# 3Phase_Inverter1.net
KiCad netlist of a schematic drawn in Altium Designer
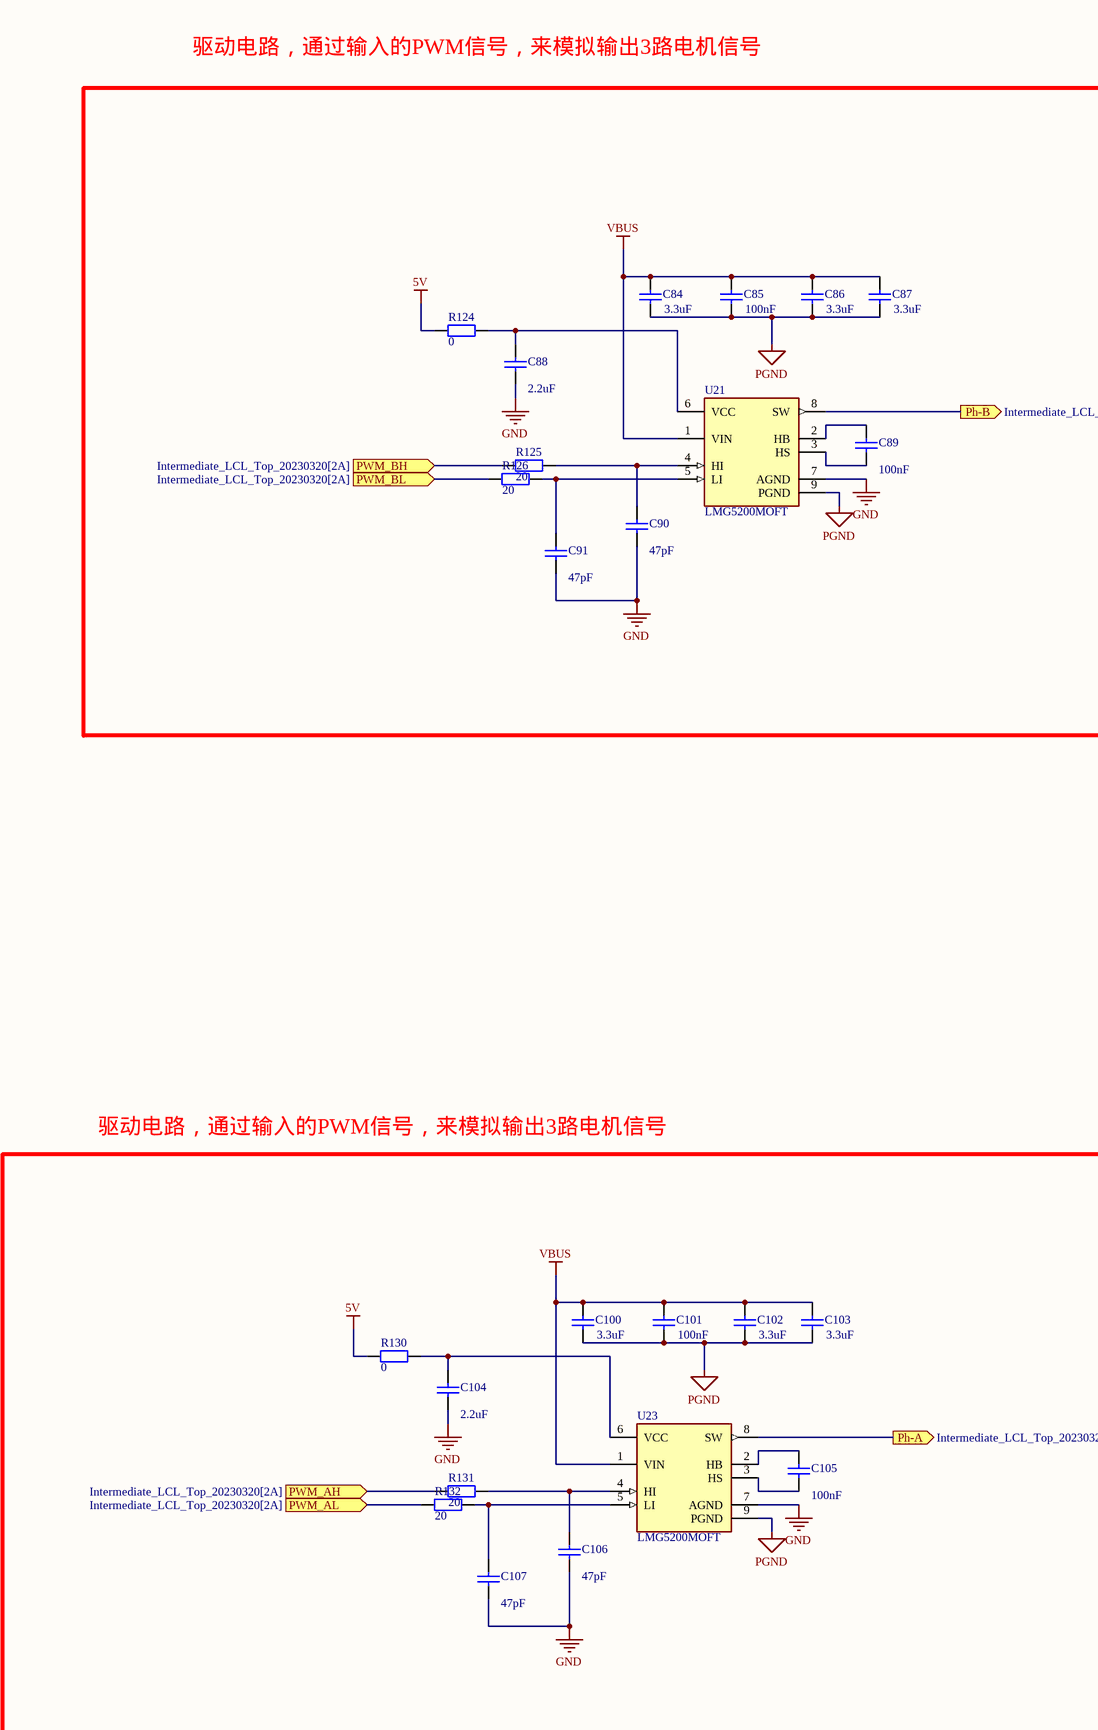
[diagram p0: 3Phase Inverter1.SchDoc, left]
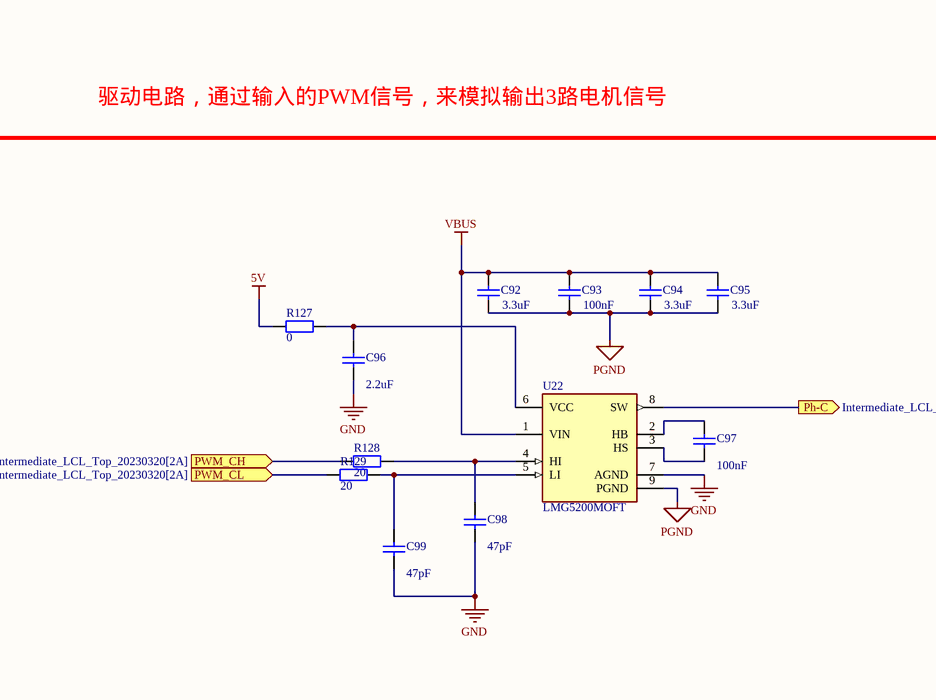
[diagram p1: 3Phase Inverter1.SchDoc, right]

(export (version "E")
  (design (tool "Eeschema 10.0.6"))
  (components
    (comp (ref "C84")
      (value "3.3uF")
      (footprint "CAPC1608X06N")
      (description "Capacitor")
      (fields (field (name "PUBLISHER") "Altium Limited"))
      (libsource (lib "aaa2") (part "Cap"))
    )
    (comp (ref "C85")
      (value "100nF")
      (footprint "CAPC1608X06N")
      (description "Capacitor")
      (fields (field (name "PUBLISHER") "Altium Limited"))
      (libsource (lib "Simscale") (part "Cap"))
    )
    (comp (ref "C86")
      (value "3.3uF")
      (footprint "CAPC1608X06N")
      (description "Capacitor")
      (fields (field (name "PUBLISHER") "Altium Limited"))
      (libsource (lib "Simscale") (part "Cap"))
    )
    (comp (ref "C87")
      (value "3.3uF")
      (footprint "CAPC1608X06N")
      (description "Capacitor")
      (fields (field (name "PUBLISHER") "Altium Limited"))
      (libsource (lib "Simscale") (part "Cap"))
    )
    (comp (ref "C88")
      (value "2.2uF")
      (footprint "CAPC1608X06N")
      (description "Capacitor")
      (fields (field (name "PUBLISHER") "Altium Limited"))
      (libsource (lib "Simscale") (part "Cap"))
    )
    (comp (ref "C89")
      (value "100nF")
      (footprint "CAPC1608X06N")
      (description "Capacitor")
      (fields (field (name "PUBLISHER") "Altium Limited"))
      (libsource (lib "Simscale") (part "Cap"))
    )
    (comp (ref "C90")
      (value "47pF")
      (footprint "CAPC1608X06N")
      (description "Capacitor")
      (fields (field (name "PUBLISHER") "Altium Limited"))
      (libsource (lib "Simscale") (part "Cap"))
    )
    (comp (ref "C91")
      (value "47pF")
      (footprint "CAPC1608X06N")
      (description "Capacitor")
      (fields (field (name "PUBLISHER") "Altium Limited"))
      (libsource (lib "Simscale") (part "Cap"))
    )
    (comp (ref "C92")
      (value "3.3uF")
      (footprint "CAPC1608X06N")
      (description "Capacitor")
      (fields (field (name "PUBLISHER") "Altium Limited"))
      (libsource (lib "aaa2") (part "Cap"))
    )
    (comp (ref "C93")
      (value "100nF")
      (footprint "CAPC1608X06N")
      (description "Capacitor")
      (fields (field (name "PUBLISHER") "Altium Limited"))
      (libsource (lib "Simscale") (part "Cap"))
    )
    (comp (ref "C94")
      (value "3.3uF")
      (footprint "CAPC1608X06N")
      (description "Capacitor")
      (fields (field (name "PUBLISHER") "Altium Limited"))
      (libsource (lib "Simscale") (part "Cap"))
    )
    (comp (ref "C95")
      (value "3.3uF")
      (footprint "CAPC1608X06N")
      (description "Capacitor")
      (fields (field (name "PUBLISHER") "Altium Limited"))
      (libsource (lib "Simscale") (part "Cap"))
    )
    (comp (ref "C96")
      (value "2.2uF")
      (footprint "CAPC1608X06N")
      (description "Capacitor")
      (fields (field (name "PUBLISHER") "Altium Limited"))
      (libsource (lib "Simscale") (part "Cap"))
    )
    (comp (ref "C97")
      (value "100nF")
      (footprint "CAPC1608X06N")
      (description "Capacitor")
      (fields (field (name "PUBLISHER") "Altium Limited"))
      (libsource (lib "Simscale") (part "Cap"))
    )
    (comp (ref "C98")
      (value "47pF")
      (footprint "CAPC1608X06N")
      (description "Capacitor")
      (fields (field (name "PUBLISHER") "Altium Limited"))
      (libsource (lib "Simscale") (part "Cap"))
    )
    (comp (ref "C99")
      (value "47pF")
      (footprint "CAPC1608X06N")
      (description "Capacitor")
      (fields (field (name "PUBLISHER") "Altium Limited"))
      (libsource (lib "Simscale") (part "Cap"))
    )
    (comp (ref "C100")
      (value "3.3uF")
      (footprint "CAPC1608X06N")
      (description "Capacitor")
      (fields (field (name "PUBLISHER") "Altium Limited"))
      (libsource (lib "aaa2") (part "Cap"))
    )
    (comp (ref "C101")
      (value "100nF")
      (footprint "CAPC1608X06N")
      (description "Capacitor")
      (fields (field (name "PUBLISHER") "Altium Limited"))
      (libsource (lib "Simscale") (part "Cap"))
    )
    (comp (ref "C102")
      (value "3.3uF")
      (footprint "CAPC1608X06N")
      (description "Capacitor")
      (fields (field (name "PUBLISHER") "Altium Limited"))
      (libsource (lib "Simscale") (part "Cap"))
    )
    (comp (ref "C103")
      (value "3.3uF")
      (footprint "CAPC1608X06N")
      (description "Capacitor")
      (fields (field (name "PUBLISHER") "Altium Limited"))
      (libsource (lib "Simscale") (part "Cap"))
    )
    (comp (ref "C104")
      (value "2.2uF")
      (footprint "CAPC1608X06N")
      (description "Capacitor")
      (fields (field (name "PUBLISHER") "Altium Limited"))
      (libsource (lib "Simscale") (part "Cap"))
    )
    (comp (ref "C105")
      (value "100nF")
      (footprint "CAPC1608X06N")
      (description "Capacitor")
      (fields (field (name "PUBLISHER") "Altium Limited"))
      (libsource (lib "Simscale") (part "Cap"))
    )
    (comp (ref "C106")
      (value "47pF")
      (footprint "CAPC1608X06N")
      (description "Capacitor")
      (fields (field (name "PUBLISHER") "Altium Limited"))
      (libsource (lib "Simscale") (part "Cap"))
    )
    (comp (ref "C107")
      (value "47pF")
      (footprint "CAPC1608X06N")
      (description "Capacitor")
      (fields (field (name "PUBLISHER") "Altium Limited"))
      (libsource (lib "Simscale") (part "Cap"))
    )
    (comp (ref "R124")
      (value "0")
      (footprint "RESC1608X05N")
      (description "贴片电阻")
      (libsource (lib "Simscale") (part "0603 100KΩ (1003) 1%_4"))
    )
    (comp (ref "R125")
      (value "20")
      (footprint "RESC1608X05N")
      (description "贴片电阻")
      (libsource (lib "Simscale") (part "0603 100KΩ (1003) 1%_4"))
    )
    (comp (ref "R126")
      (value "20")
      (footprint "RESC1608X05N")
      (description "贴片电阻")
      (libsource (lib "Simscale") (part "0603 100KΩ (1003) 1%_4"))
    )
    (comp (ref "R127")
      (value "0")
      (footprint "RESC1608X05N")
      (description "贴片电阻")
      (libsource (lib "Simscale") (part "0603 100KΩ (1003) 1%_4"))
    )
    (comp (ref "R128")
      (value "20")
      (footprint "RESC1608X05N")
      (description "贴片电阻")
      (libsource (lib "Simscale") (part "0603 100KΩ (1003) 1%_4"))
    )
    (comp (ref "R129")
      (value "20")
      (footprint "RESC1608X05N")
      (description "贴片电阻")
      (libsource (lib "Simscale") (part "0603 100KΩ (1003) 1%_4"))
    )
    (comp (ref "R130")
      (value "0")
      (footprint "RESC1608X05N")
      (description "贴片电阻")
      (libsource (lib "Simscale") (part "0603 100KΩ (1003) 1%_4"))
    )
    (comp (ref "R131")
      (value "20")
      (footprint "RESC1608X05N")
      (description "贴片电阻")
      (libsource (lib "Simscale") (part "0603 100KΩ (1003) 1%_4"))
    )
    (comp (ref "R132")
      (value "20")
      (footprint "RESC1608X05N")
      (description "贴片电阻")
      (libsource (lib "Simscale") (part "0603 100KΩ (1003) 1%_4"))
    )
    (comp (ref "U21")
      (value "LMG5200MOFT")
      (footprint "FP-MOF0009A-MFG")
      (description "None")
      (libsource (lib "Altium Content Vault") (part "e04ca9006c06531c2d1851f29eb7844"))
    )
    (comp (ref "U22")
      (value "LMG5200MOFT")
      (footprint "FP-MOF0009A-MFG")
      (description "None")
      (libsource (lib "Altium Content Vault") (part "e04ca9006c06531c2d1851f29eb7844"))
    )
    (comp (ref "U23")
      (value "LMG5200MOFT")
      (footprint "FP-MOF0009A-MFG")
      (description "None")
      (libsource (lib "Altium Content Vault") (part "e04ca9006c06531c2d1851f29eb7844"))
    )
  )
  (nets
    (net (code "1") (name "/PWM_AH") (class "Default")
      (node (ref "R131") (pin "2") (pinfunction "2_2") (pintype "passive"))
    )
    (net (code "2") (name "/PWM_AL") (class "Default")
      (node (ref "R132") (pin "2") (pinfunction "2_2") (pintype "passive"))
    )
    (net (code "3") (name "/PWM_BH") (class "Default")
      (node (ref "R125") (pin "2") (pinfunction "2_2") (pintype "passive"))
    )
    (net (code "4") (name "/PWM_BL") (class "Default")
      (node (ref "R126") (pin "2") (pinfunction "2_2") (pintype "passive"))
    )
    (net (code "5") (name "/PWM_CH") (class "Default")
      (node (ref "R128") (pin "2") (pinfunction "2_2") (pintype "passive"))
    )
    (net (code "6") (name "/PWM_CL") (class "Default")
      (node (ref "R129") (pin "2") (pinfunction "2_2") (pintype "passive"))
    )
    (net (code "7") (name "/Ph-A") (class "Default")
      (node (ref "U23") (pin "8") (pinfunction "SW_8") (pintype "output"))
    )
    (net (code "8") (name "/Ph-B") (class "Default")
      (node (ref "U21") (pin "8") (pinfunction "SW_8") (pintype "output"))
    )
    (net (code "9") (name "/Ph-C") (class "Default")
      (node (ref "U22") (pin "8") (pinfunction "SW_8") (pintype "output"))
    )
    (net (code "10") (name "5V") (class "Default")
      (node (ref "R124") (pin "2") (pinfunction "2_2") (pintype "passive"))
      (node (ref "R127") (pin "2") (pinfunction "2_2") (pintype "passive"))
      (node (ref "R130") (pin "2") (pinfunction "2_2") (pintype "passive"))
    )
    (net (code "11") (name "GND") (class "Default")
      (node (ref "C104") (pin "1") (pinfunction "1_1") (pintype "passive"))
      (node (ref "C106") (pin "2") (pinfunction "2_2") (pintype "passive"))
      (node (ref "C107") (pin "2") (pinfunction "2_2") (pintype "passive"))
      (node (ref "C88") (pin "1") (pinfunction "1_1") (pintype "passive"))
      (node (ref "C90") (pin "2") (pinfunction "2_2") (pintype "passive"))
      (node (ref "C91") (pin "2") (pinfunction "2_2") (pintype "passive"))
      (node (ref "C96") (pin "1") (pinfunction "1_1") (pintype "passive"))
      (node (ref "C98") (pin "2") (pinfunction "2_2") (pintype "passive"))
      (node (ref "C99") (pin "2") (pinfunction "2_2") (pintype "passive"))
      (node (ref "U21") (pin "7") (pinfunction "AGND_7") (pintype "power_in"))
      (node (ref "U22") (pin "7") (pinfunction "AGND_7") (pintype "power_in"))
      (node (ref "U23") (pin "7") (pinfunction "AGND_7") (pintype "power_in"))
    )
    (net (code "12") (name "Net-(U21-HB)") (class "Default")
      (node (ref "C89") (pin "1") (pinfunction "1_1") (pintype "passive"))
      (node (ref "U21") (pin "2") (pinfunction "HB_2") (pintype "passive"))
    )
    (net (code "13") (name "Net-(U21-HI)") (class "Default")
      (node (ref "C90") (pin "1") (pinfunction "1_1") (pintype "passive"))
      (node (ref "R125") (pin "1") (pinfunction "1_1") (pintype "passive"))
      (node (ref "U21") (pin "4") (pinfunction "HI_4") (pintype "input"))
    )
    (net (code "14") (name "Net-(U21-HS)") (class "Default")
      (node (ref "C89") (pin "2") (pinfunction "2_2") (pintype "passive"))
      (node (ref "U21") (pin "3") (pinfunction "HS_3") (pintype "passive"))
    )
    (net (code "15") (name "Net-(U21-LI)") (class "Default")
      (node (ref "C91") (pin "1") (pinfunction "1_1") (pintype "passive"))
      (node (ref "R126") (pin "1") (pinfunction "1_1") (pintype "passive"))
      (node (ref "U21") (pin "5") (pinfunction "LI_5") (pintype "input"))
    )
    (net (code "16") (name "Net-(U21-VCC)") (class "Default")
      (node (ref "C88") (pin "2") (pinfunction "2_2") (pintype "passive"))
      (node (ref "R124") (pin "1") (pinfunction "1_1") (pintype "passive"))
      (node (ref "U21") (pin "6") (pinfunction "VCC_6") (pintype "power_in"))
    )
    (net (code "17") (name "Net-(U22-HB)") (class "Default")
      (node (ref "C97") (pin "1") (pinfunction "1_1") (pintype "passive"))
      (node (ref "U22") (pin "2") (pinfunction "HB_2") (pintype "passive"))
    )
    (net (code "18") (name "Net-(U22-HI)") (class "Default")
      (node (ref "C98") (pin "1") (pinfunction "1_1") (pintype "passive"))
      (node (ref "R128") (pin "1") (pinfunction "1_1") (pintype "passive"))
      (node (ref "U22") (pin "4") (pinfunction "HI_4") (pintype "input"))
    )
    (net (code "19") (name "Net-(U22-HS)") (class "Default")
      (node (ref "C97") (pin "2") (pinfunction "2_2") (pintype "passive"))
      (node (ref "U22") (pin "3") (pinfunction "HS_3") (pintype "passive"))
    )
    (net (code "20") (name "Net-(U22-LI)") (class "Default")
      (node (ref "C99") (pin "1") (pinfunction "1_1") (pintype "passive"))
      (node (ref "R129") (pin "1") (pinfunction "1_1") (pintype "passive"))
      (node (ref "U22") (pin "5") (pinfunction "LI_5") (pintype "input"))
    )
    (net (code "21") (name "Net-(U22-VCC)") (class "Default")
      (node (ref "C96") (pin "2") (pinfunction "2_2") (pintype "passive"))
      (node (ref "R127") (pin "1") (pinfunction "1_1") (pintype "passive"))
      (node (ref "U22") (pin "6") (pinfunction "VCC_6") (pintype "power_in"))
    )
    (net (code "22") (name "Net-(U23-HB)") (class "Default")
      (node (ref "C105") (pin "1") (pinfunction "1_1") (pintype "passive"))
      (node (ref "U23") (pin "2") (pinfunction "HB_2") (pintype "passive"))
    )
    (net (code "23") (name "Net-(U23-HI)") (class "Default")
      (node (ref "C106") (pin "1") (pinfunction "1_1") (pintype "passive"))
      (node (ref "R131") (pin "1") (pinfunction "1_1") (pintype "passive"))
      (node (ref "U23") (pin "4") (pinfunction "HI_4") (pintype "input"))
    )
    (net (code "24") (name "Net-(U23-HS)") (class "Default")
      (node (ref "C105") (pin "2") (pinfunction "2_2") (pintype "passive"))
      (node (ref "U23") (pin "3") (pinfunction "HS_3") (pintype "passive"))
    )
    (net (code "25") (name "Net-(U23-LI)") (class "Default")
      (node (ref "C107") (pin "1") (pinfunction "1_1") (pintype "passive"))
      (node (ref "R132") (pin "1") (pinfunction "1_1") (pintype "passive"))
      (node (ref "U23") (pin "5") (pinfunction "LI_5") (pintype "input"))
    )
    (net (code "26") (name "Net-(U23-VCC)") (class "Default")
      (node (ref "C104") (pin "2") (pinfunction "2_2") (pintype "passive"))
      (node (ref "R130") (pin "1") (pinfunction "1_1") (pintype "passive"))
      (node (ref "U23") (pin "6") (pinfunction "VCC_6") (pintype "power_in"))
    )
    (net (code "27") (name "PGND") (class "Default")
      (node (ref "C100") (pin "1") (pinfunction "1_1") (pintype "passive"))
      (node (ref "C101") (pin "2") (pinfunction "2_2") (pintype "passive"))
      (node (ref "C102") (pin "1") (pinfunction "1_1") (pintype "passive"))
      (node (ref "C103") (pin "1") (pinfunction "1_1") (pintype "passive"))
      (node (ref "C84") (pin "1") (pinfunction "1_1") (pintype "passive"))
      (node (ref "C85") (pin "2") (pinfunction "2_2") (pintype "passive"))
      (node (ref "C86") (pin "1") (pinfunction "1_1") (pintype "passive"))
      (node (ref "C87") (pin "1") (pinfunction "1_1") (pintype "passive"))
      (node (ref "C92") (pin "1") (pinfunction "1_1") (pintype "passive"))
      (node (ref "C93") (pin "2") (pinfunction "2_2") (pintype "passive"))
      (node (ref "C94") (pin "1") (pinfunction "1_1") (pintype "passive"))
      (node (ref "C95") (pin "1") (pinfunction "1_1") (pintype "passive"))
      (node (ref "U21") (pin "9") (pinfunction "PGND_9") (pintype "power_in"))
      (node (ref "U22") (pin "9") (pinfunction "PGND_9") (pintype "power_in"))
      (node (ref "U23") (pin "9") (pinfunction "PGND_9") (pintype "power_in"))
    )
    (net (code "28") (name "VBUS") (class "Default")
      (node (ref "C100") (pin "2") (pinfunction "2_2") (pintype "passive"))
      (node (ref "C101") (pin "1") (pinfunction "1_1") (pintype "passive"))
      (node (ref "C102") (pin "2") (pinfunction "2_2") (pintype "passive"))
      (node (ref "C103") (pin "2") (pinfunction "2_2") (pintype "passive"))
      (node (ref "C84") (pin "2") (pinfunction "2_2") (pintype "passive"))
      (node (ref "C85") (pin "1") (pinfunction "1_1") (pintype "passive"))
      (node (ref "C86") (pin "2") (pinfunction "2_2") (pintype "passive"))
      (node (ref "C87") (pin "2") (pinfunction "2_2") (pintype "passive"))
      (node (ref "C92") (pin "2") (pinfunction "2_2") (pintype "passive"))
      (node (ref "C93") (pin "1") (pinfunction "1_1") (pintype "passive"))
      (node (ref "C94") (pin "2") (pinfunction "2_2") (pintype "passive"))
      (node (ref "C95") (pin "2") (pinfunction "2_2") (pintype "passive"))
      (node (ref "U21") (pin "1") (pinfunction "VIN_1") (pintype "power_in"))
      (node (ref "U22") (pin "1") (pinfunction "VIN_1") (pintype "power_in"))
      (node (ref "U23") (pin "1") (pinfunction "VIN_1") (pintype "power_in"))
    )
  )
)
